# Grove_-_Multichannel_Gas_Sensor_v1_0.net
KiCad netlist of a schematic drawn in EAGLE
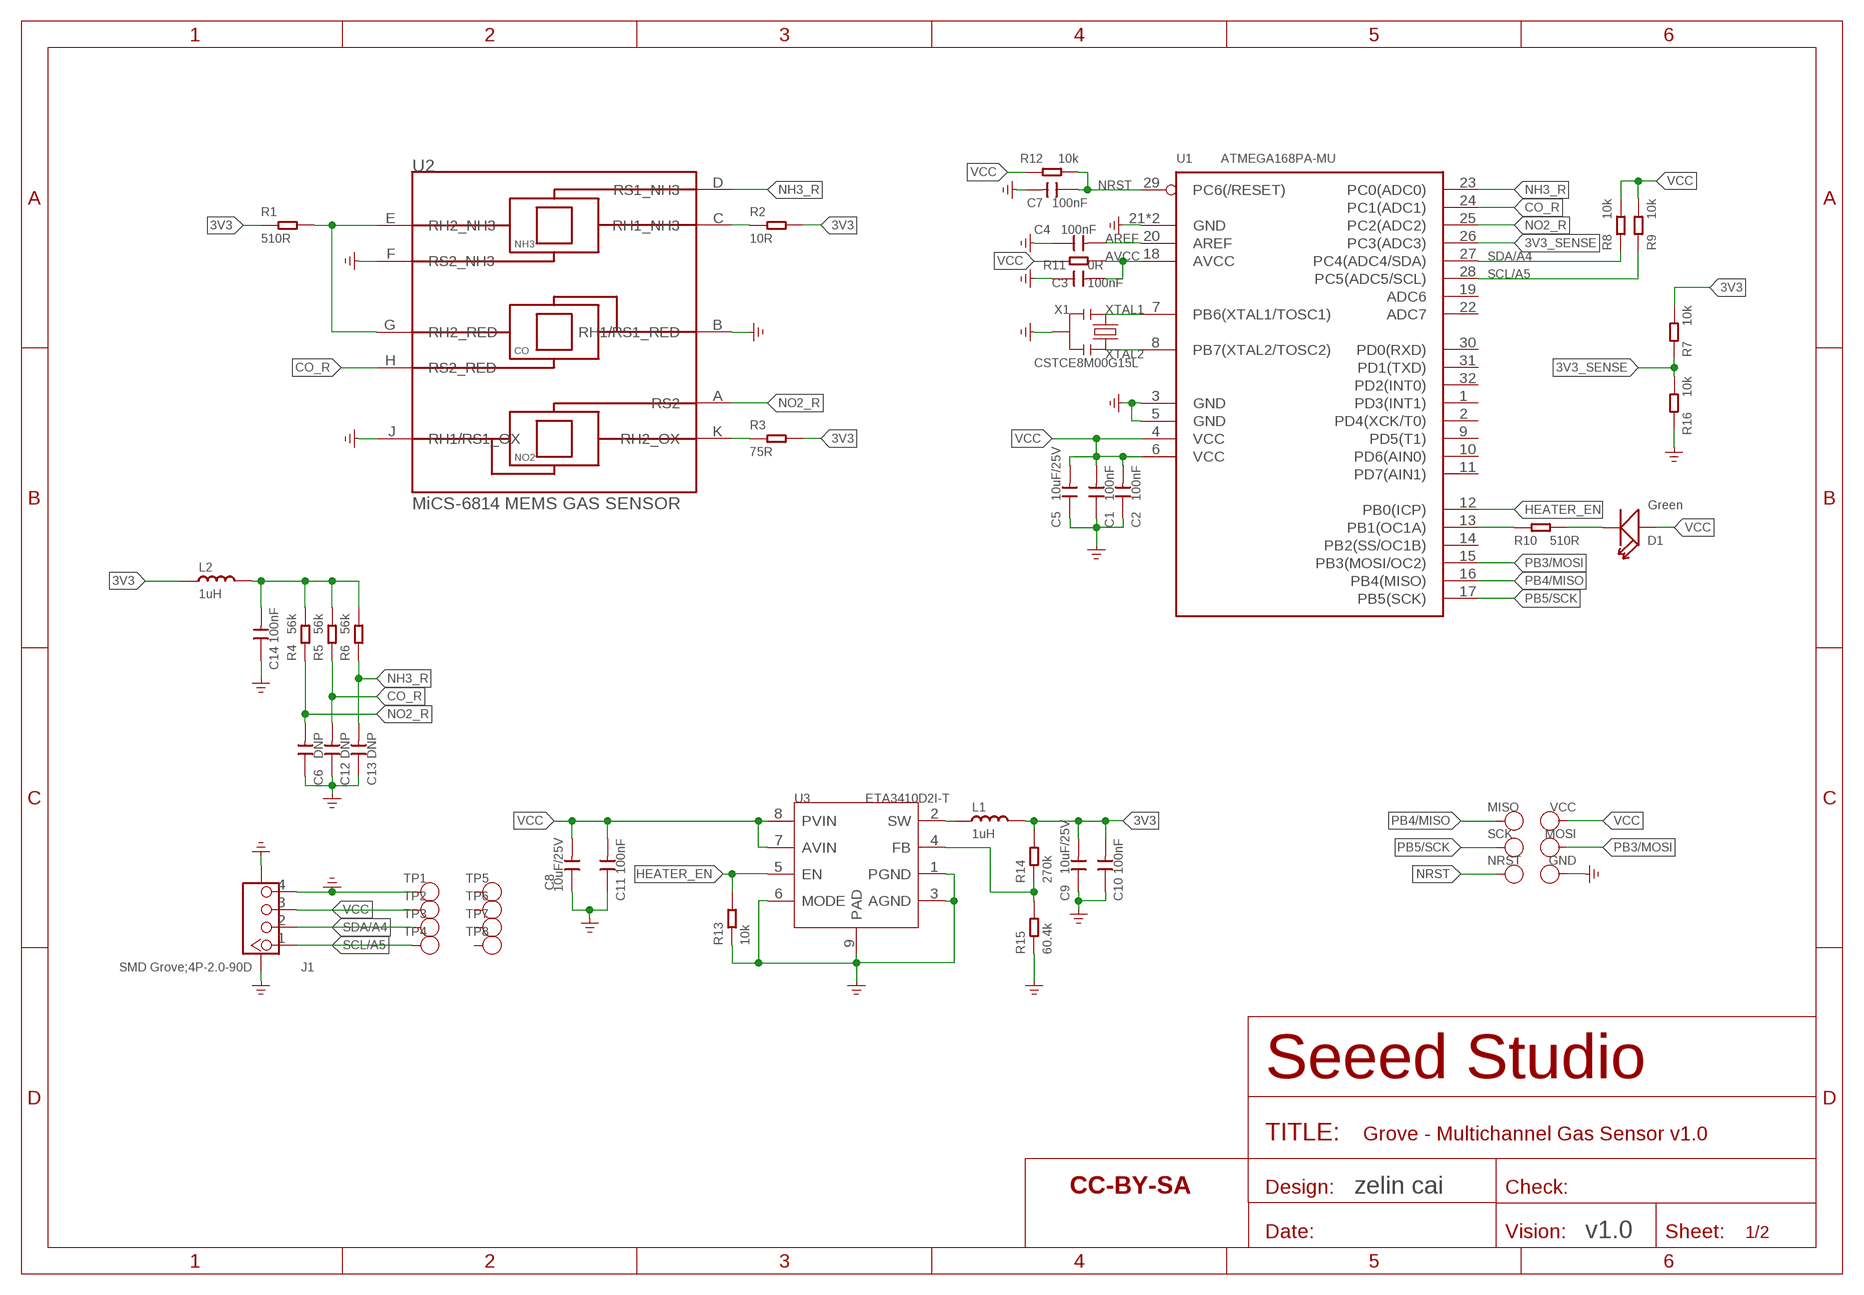
[diagram p0: schematic, sheet 1]

(export (version "E")
  (design (tool "Eeschema 10.0.6"))
  (components
    (comp (ref "C1")
      (value "100nF")
      (footprint "eagle-import:C0402")
      (libsource (lib "eagle-import") (part "CAP-0402"))
    )
    (comp (ref "C2")
      (value "100nF")
      (footprint "eagle-import:C0402")
      (libsource (lib "eagle-import") (part "CAP-0402"))
    )
    (comp (ref "C3")
      (value "100nF")
      (footprint "eagle-import:C0402")
      (libsource (lib "eagle-import") (part "CAP-0402"))
    )
    (comp (ref "C4")
      (value "100nF")
      (footprint "eagle-import:C0402")
      (libsource (lib "eagle-import") (part "CAP-0402"))
    )
    (comp (ref "C5")
      (value "10uF/25V")
      (footprint "eagle-import:C0805")
      (libsource (lib "eagle-import") (part "CAP-0805"))
    )
    (comp (ref "C6")
      (value "DNP")
      (footprint "eagle-import:C0402")
      (libsource (lib "eagle-import") (part "CAP-0402"))
    )
    (comp (ref "C7")
      (value "100nF")
      (footprint "eagle-import:C0402")
      (libsource (lib "eagle-import") (part "CAP-0402"))
    )
    (comp (ref "C8")
      (value "10uF/25V")
      (footprint "eagle-import:C0805")
      (libsource (lib "eagle-import") (part "CAP-0805"))
    )
    (comp (ref "C9")
      (value "10uF/25V")
      (footprint "eagle-import:C0805")
      (libsource (lib "eagle-import") (part "CAP-0805"))
    )
    (comp (ref "C10")
      (value "100nF")
      (footprint "eagle-import:C0402")
      (libsource (lib "eagle-import") (part "CAP-0402"))
    )
    (comp (ref "C11")
      (value "100nF")
      (footprint "eagle-import:C0402")
      (libsource (lib "eagle-import") (part "CAP-0402"))
    )
    (comp (ref "C12")
      (value "DNP")
      (footprint "eagle-import:C0402")
      (libsource (lib "eagle-import") (part "CAP-0402"))
    )
    (comp (ref "C13")
      (value "DNP")
      (footprint "eagle-import:C0402")
      (libsource (lib "eagle-import") (part "CAP-0402"))
    )
    (comp (ref "C14")
      (value "100nF")
      (footprint "eagle-import:C0402")
      (libsource (lib "eagle-import") (part "CAP-0402"))
    )
    (comp (ref "D1")
      (value "Green")
      (footprint "eagle-import:LED-0402")
      (libsource (lib "eagle-import") (part "LED'0402'"))
    )
    (comp (ref "GND")
      (value "GND")
      (footprint "eagle-import:TP-D45MIL")
      (fields (field (name "PARTNO") "DNP"))
      (libsource (lib "eagle-import") (part "TEST-POINT'4545'"))
    )
    (comp (ref "J1")
      (value "SMD Grove;4P-2.0-90D")
      (footprint "eagle-import:HW4-SMD-2.0-90D")
      (libsource (lib "eagle-import") (part "GROVE-CONNECTOR-SMD'90D'"))
    )
    (comp (ref "L1")
      (value "1uH")
      (footprint "eagle-import:L0603")
      (libsource (lib "eagle-import") (part "INDUCTOR/FERRITE-BEAD'0603'"))
    )
    (comp (ref "L2")
      (value "1uH")
      (footprint "eagle-import:L0603")
      (libsource (lib "eagle-import") (part "INDUCTOR/FERRITE-BEAD'0603'"))
    )
    (comp (ref "MISO")
      (value "MISO")
      (footprint "eagle-import:TP-D45MIL")
      (fields (field (name "PARTNO") "DNP"))
      (libsource (lib "eagle-import") (part "TEST-POINT'4545'"))
    )
    (comp (ref "MOSI")
      (value "MOSI")
      (footprint "eagle-import:TP-D45MIL")
      (fields (field (name "PARTNO") "DNP"))
      (libsource (lib "eagle-import") (part "TEST-POINT'4545'"))
    )
    (comp (ref "NRST")
      (value "NRST")
      (footprint "eagle-import:TP-D45MIL")
      (fields (field (name "PARTNO") "DNP"))
      (libsource (lib "eagle-import") (part "TEST-POINT'4545'"))
    )
    (comp (ref "R1")
      (value "510R")
      (footprint "eagle-import:R0402")
      (libsource (lib "eagle-import") (part "RES-0402"))
    )
    (comp (ref "R2")
      (value "10R")
      (footprint "eagle-import:R0402")
      (libsource (lib "eagle-import") (part "RES-0402"))
    )
    (comp (ref "R3")
      (value "75R")
      (footprint "eagle-import:R0402")
      (libsource (lib "eagle-import") (part "RES-0402"))
    )
    (comp (ref "R4")
      (value "56k")
      (footprint "eagle-import:R0402")
      (libsource (lib "eagle-import") (part "RES-0402"))
    )
    (comp (ref "R5")
      (value "56k")
      (footprint "eagle-import:R0402")
      (libsource (lib "eagle-import") (part "RES-0402"))
    )
    (comp (ref "R6")
      (value "56k")
      (footprint "eagle-import:R0402")
      (libsource (lib "eagle-import") (part "RES-0402"))
    )
    (comp (ref "R7")
      (value "10k")
      (footprint "eagle-import:R0402")
      (libsource (lib "eagle-import") (part "RES-0402"))
    )
    (comp (ref "R8")
      (value "10k")
      (footprint "eagle-import:R0402")
      (libsource (lib "eagle-import") (part "RES-0402"))
    )
    (comp (ref "R9")
      (value "10k")
      (footprint "eagle-import:R0402")
      (libsource (lib "eagle-import") (part "RES-0402"))
    )
    (comp (ref "R10")
      (value "510R")
      (footprint "eagle-import:R0402")
      (libsource (lib "eagle-import") (part "RES-0402"))
    )
    (comp (ref "R11")
      (value "0R")
      (footprint "eagle-import:R0402")
      (libsource (lib "eagle-import") (part "RES-0402"))
    )
    (comp (ref "R12")
      (value "10k")
      (footprint "eagle-import:R0402")
      (libsource (lib "eagle-import") (part "RES-0402"))
    )
    (comp (ref "R13")
      (value "10k")
      (footprint "eagle-import:R0402")
      (libsource (lib "eagle-import") (part "RES-0402"))
    )
    (comp (ref "R14")
      (value "270k")
      (footprint "eagle-import:R0402")
      (libsource (lib "eagle-import") (part "RES-0402"))
    )
    (comp (ref "R15")
      (value "60.4k")
      (footprint "eagle-import:R0402")
      (libsource (lib "eagle-import") (part "RES-0402"))
    )
    (comp (ref "R16")
      (value "10k")
      (footprint "eagle-import:R0402")
      (libsource (lib "eagle-import") (part "RES-0402"))
    )
    (comp (ref "SCK")
      (value "SCK")
      (footprint "eagle-import:TP-D45MIL")
      (fields (field (name "PARTNO") "DNP"))
      (libsource (lib "eagle-import") (part "TEST-POINT'4545'"))
    )
    (comp (ref "TP1")
      (value "GND")
      (footprint "eagle-import:TP-D45MIL")
      (fields (field (name "PARTNO") "DNP"))
      (libsource (lib "eagle-import") (part "TEST-POINT'4545'"))
    )
    (comp (ref "TP2")
      (value "VCC")
      (footprint "eagle-import:TP-D45MIL")
      (fields (field (name "PARTNO") "DNP"))
      (libsource (lib "eagle-import") (part "TEST-POINT'4545'"))
    )
    (comp (ref "TP3")
      (value "SDA")
      (footprint "eagle-import:TP-D45MIL")
      (fields (field (name "PARTNO") "DNP"))
      (libsource (lib "eagle-import") (part "TEST-POINT'4545'"))
    )
    (comp (ref "TP4")
      (value "SCL")
      (footprint "eagle-import:TP-D45MIL")
      (fields (field (name "PARTNO") "DNP"))
      (libsource (lib "eagle-import") (part "TEST-POINT'4545'"))
    )
    (comp (ref "TP5")
      (value "NC")
      (footprint "eagle-import:TP-D45MIL")
      (fields (field (name "PARTNO") "DNP"))
      (libsource (lib "eagle-import") (part "TEST-POINT'4545'"))
    )
    (comp (ref "TP6")
      (value "NC")
      (footprint "eagle-import:TP-D45MIL")
      (fields (field (name "PARTNO") "DNP"))
      (libsource (lib "eagle-import") (part "TEST-POINT'4545'"))
    )
    (comp (ref "TP7")
      (value "NC")
      (footprint "eagle-import:TP-D45MIL")
      (fields (field (name "PARTNO") "DNP"))
      (libsource (lib "eagle-import") (part "TEST-POINT'4545'"))
    )
    (comp (ref "TP8")
      (value "NC")
      (footprint "eagle-import:TP-D45MIL")
      (fields (field (name "PARTNO") "DNP"))
      (libsource (lib "eagle-import") (part "TEST-POINT'4545'"))
    )
    (comp (ref "U$1")
      (value "Xadow-Multichanel Gas Sensor")
      (footprint "eagle-import:SEEEDSTUDIO-PCB-FRAME")
      (libsource (lib "eagle-import") (part "SEEEDSTUDIO-OPEN-SCH-FRAME"))
    )
    (comp (ref "U1")
      (value "ATMEGA168PA-MU")
      (footprint "eagle-import:QFN32G-0.5-5X5MM")
      (libsource (lib "eagle-import") (part "MCU-ATMEGA8/168/328MU"))
    )
    (comp (ref "U2")
      (value "MiCS-6814")
      (footprint "eagle-import:MICS-6814")
      (libsource (lib "eagle-import") (part "MICS-6814"))
    )
    (comp (ref "U3")
      (value "ETA3410D2I-T")
      (footprint "eagle-import:DFN8G-0.5-2X2MM")
      (libsource (lib "eagle-import") (part "CONVERTER-ETA3410"))
    )
    (comp (ref "VCC")
      (value "VCC")
      (footprint "eagle-import:TP-D45MIL")
      (fields (field (name "PARTNO") "DNP"))
      (libsource (lib "eagle-import") (part "TEST-POINT'4545'"))
    )
    (comp (ref "X1")
      (value "CSTCE8M00G15L")
      (footprint "eagle-import:RESONATOR3-SMD-3.6X1.3X0.8MM")
      (libsource (lib "eagle-import") (part "CRYSTAL-RESONATOR'SMD'"))
    )
  )
  (nets
    (net (code "1") (name "3V3") (class "Default")
      (node (ref "C10") (pin "2") (pinfunction "2_2") (pintype "passive"))
      (node (ref "C9") (pin "2") (pinfunction "2_2") (pintype "passive"))
      (node (ref "L1") (pin "2") (pinfunction "2_2") (pintype "passive"))
      (node (ref "L2") (pin "1") (pinfunction "1_1") (pintype "passive"))
      (node (ref "R1") (pin "1") (pinfunction "1_1") (pintype "passive"))
      (node (ref "R14") (pin "2") (pinfunction "2_2") (pintype "passive"))
      (node (ref "R2") (pin "2") (pinfunction "2_2") (pintype "passive"))
      (node (ref "R3") (pin "2") (pinfunction "2_2") (pintype "passive"))
      (node (ref "R7") (pin "1") (pinfunction "1_1") (pintype "passive"))
    )
    (net (code "2") (name "3V3_SENSE") (class "Default")
      (node (ref "R16") (pin "1") (pinfunction "1_1") (pintype "passive"))
      (node (ref "R7") (pin "2") (pinfunction "2_2") (pintype "passive"))
      (node (ref "U1") (pin "26") (pinfunction "PC3(ADC3)_26") (pintype "bidirectional"))
    )
    (net (code "3") (name "AREF") (class "Default")
      (node (ref "C4") (pin "2") (pinfunction "2_2") (pintype "passive"))
      (node (ref "U1") (pin "20") (pinfunction "AREF_20") (pintype "bidirectional"))
    )
    (net (code "4") (name "AVCC") (class "Default")
      (node (ref "C3") (pin "2") (pinfunction "2_2") (pintype "passive"))
      (node (ref "R11") (pin "2") (pinfunction "2_2") (pintype "passive"))
      (node (ref "U1") (pin "18") (pinfunction "AVCC_18") (pintype "bidirectional"))
    )
    (net (code "5") (name "CO_R") (class "Default")
      (node (ref "C12") (pin "2") (pinfunction "2_2") (pintype "passive"))
      (node (ref "R5") (pin "1") (pinfunction "1_1") (pintype "passive"))
      (node (ref "U1") (pin "24") (pinfunction "PC1(ADC1)_24") (pintype "bidirectional"))
      (node (ref "U2") (pin "H") (pinfunction "RS2_RED_H") (pintype "bidirectional"))
    )
    (net (code "6") (name "GND") (class "Default")
      (node (ref "C1") (pin "1") (pinfunction "1_1") (pintype "passive"))
      (node (ref "C10") (pin "1") (pinfunction "1_1") (pintype "passive"))
      (node (ref "C11") (pin "1") (pinfunction "1_1") (pintype "passive"))
      (node (ref "C12") (pin "1") (pinfunction "1_1") (pintype "passive"))
      (node (ref "C13") (pin "1") (pinfunction "1_1") (pintype "passive"))
      (node (ref "C14") (pin "1") (pinfunction "1_1") (pintype "passive"))
      (node (ref "C2") (pin "1") (pinfunction "1_1") (pintype "passive"))
      (node (ref "C3") (pin "1") (pinfunction "1_1") (pintype "passive"))
      (node (ref "C4") (pin "1") (pinfunction "1_1") (pintype "passive"))
      (node (ref "C5") (pin "1") (pinfunction "1_1") (pintype "passive"))
      (node (ref "C6") (pin "1") (pinfunction "1_1") (pintype "passive"))
      (node (ref "C7") (pin "2") (pinfunction "2_2") (pintype "passive"))
      (node (ref "C8") (pin "1") (pinfunction "1_1") (pintype "passive"))
      (node (ref "C9") (pin "1") (pinfunction "1_1") (pintype "passive"))
      (node (ref "GND") (pin "T") (pinfunction "T_T") (pintype "bidirectional"))
      (node (ref "J1") (pin "4") (pinfunction "4_4") (pintype "bidirectional"))
      (node (ref "J1") (pin "SS1") (pinfunction "SS1_SS1") (pintype "bidirectional"))
      (node (ref "J1") (pin "SS2") (pinfunction "SS2_SS2") (pintype "bidirectional"))
      (node (ref "R13") (pin "1") (pinfunction "1_1") (pintype "passive"))
      (node (ref "R15") (pin "1") (pinfunction "1_1") (pintype "passive"))
      (node (ref "R16") (pin "2") (pinfunction "2_2") (pintype "passive"))
      (node (ref "TP1") (pin "T") (pinfunction "T_T") (pintype "bidirectional"))
      (node (ref "U1") (pin "21") (pinfunction "GND_21") (pintype "bidirectional"))
      (node (ref "U1") (pin "3") (pinfunction "GND_3") (pintype "bidirectional"))
      (node (ref "U1") (pin "33") (pinfunction "GND_33") (pintype "bidirectional"))
      (node (ref "U1") (pin "5") (pinfunction "GND_5") (pintype "bidirectional"))
      (node (ref "U2") (pin "B") (pinfunction "RH1/RS1_RED_B") (pintype "bidirectional"))
      (node (ref "U2") (pin "F") (pinfunction "RS2_NH3_F") (pintype "bidirectional"))
      (node (ref "U2") (pin "J") (pinfunction "RH1/RS1_OX_J") (pintype "bidirectional"))
      (node (ref "U3") (pin "1") (pinfunction "PGND_1") (pintype "bidirectional"))
      (node (ref "U3") (pin "3") (pinfunction "AGND_3") (pintype "bidirectional"))
      (node (ref "U3") (pin "6") (pinfunction "MODE_6") (pintype "bidirectional"))
      (node (ref "U3") (pin "9") (pinfunction "PAD_9") (pintype "bidirectional"))
      (node (ref "X1") (pin "2") (pinfunction "2_2") (pintype "passive"))
    )
    (net (code "7") (name "HEATER_EN") (class "Default")
      (node (ref "R13") (pin "2") (pinfunction "2_2") (pintype "passive"))
      (node (ref "U1") (pin "12") (pinfunction "PB0(ICP)_12") (pintype "bidirectional"))
      (node (ref "U3") (pin "5") (pinfunction "EN_5") (pintype "bidirectional"))
    )
    (net (code "8") (name "NH3_R") (class "Default")
      (node (ref "C13") (pin "2") (pinfunction "2_2") (pintype "passive"))
      (node (ref "R6") (pin "1") (pinfunction "1_1") (pintype "passive"))
      (node (ref "U1") (pin "23") (pinfunction "PC0(ADC0)_23") (pintype "bidirectional"))
      (node (ref "U2") (pin "D") (pinfunction "RS1_NH3_D") (pintype "bidirectional"))
    )
    (net (code "9") (name "NO2_R") (class "Default")
      (node (ref "C6") (pin "2") (pinfunction "2_2") (pintype "passive"))
      (node (ref "R4") (pin "1") (pinfunction "1_1") (pintype "passive"))
      (node (ref "U1") (pin "25") (pinfunction "PC2(ADC2)_25") (pintype "bidirectional"))
      (node (ref "U2") (pin "A") (pinfunction "RS2_A") (pintype "bidirectional"))
    )
    (net (code "10") (name "NRST") (class "Default")
      (node (ref "C7") (pin "1") (pinfunction "1_1") (pintype "passive"))
      (node (ref "NRST") (pin "T") (pinfunction "T_T") (pintype "bidirectional"))
      (node (ref "R12") (pin "1") (pinfunction "1_1") (pintype "passive"))
      (node (ref "U1") (pin "29") (pinfunction "PC6(/RESET)_29") (pintype "bidirectional"))
    )
    (net (code "11") (name "Net-(C14-Pad2)") (class "Default")
      (node (ref "C14") (pin "2") (pinfunction "2_2") (pintype "passive"))
      (node (ref "L2") (pin "2") (pinfunction "2_2") (pintype "passive"))
      (node (ref "R4") (pin "2") (pinfunction "2_2") (pintype "passive"))
      (node (ref "R5") (pin "2") (pinfunction "2_2") (pintype "passive"))
      (node (ref "R6") (pin "2") (pinfunction "2_2") (pintype "passive"))
    )
    (net (code "12") (name "Net-(D1-Pad-)") (class "Default")
      (node (ref "D1") (pin "-") (pinfunction "-_-") (pintype "passive"))
      (node (ref "R10") (pin "2") (pinfunction "2_2") (pintype "passive"))
    )
    (net (code "13") (name "Net-(U1-PB1(OC1A))") (class "Default")
      (node (ref "R10") (pin "1") (pinfunction "1_1") (pintype "passive"))
      (node (ref "U1") (pin "13") (pinfunction "PB1(OC1A)_13") (pintype "bidirectional"))
    )
    (net (code "14") (name "Net-(U2-RH1_NH3)") (class "Default")
      (node (ref "R2") (pin "1") (pinfunction "1_1") (pintype "passive"))
      (node (ref "U2") (pin "C") (pinfunction "RH1_NH3_C") (pintype "bidirectional"))
    )
    (net (code "15") (name "Net-(U2-RH2_NH3)") (class "Default")
      (node (ref "R1") (pin "2") (pinfunction "2_2") (pintype "passive"))
      (node (ref "U2") (pin "E") (pinfunction "RH2_NH3_E") (pintype "bidirectional"))
      (node (ref "U2") (pin "G") (pinfunction "RH2_RED_G") (pintype "bidirectional"))
    )
    (net (code "16") (name "Net-(U2-RH2_OX)") (class "Default")
      (node (ref "R3") (pin "1") (pinfunction "1_1") (pintype "passive"))
      (node (ref "U2") (pin "K") (pinfunction "RH2_OX_K") (pintype "bidirectional"))
    )
    (net (code "17") (name "Net-(U3-FB)") (class "Default")
      (node (ref "R14") (pin "1") (pinfunction "1_1") (pintype "passive"))
      (node (ref "R15") (pin "2") (pinfunction "2_2") (pintype "passive"))
      (node (ref "U3") (pin "4") (pinfunction "FB_4") (pintype "bidirectional"))
    )
    (net (code "18") (name "Net-(U3-SW)") (class "Default")
      (node (ref "L1") (pin "1") (pinfunction "1_1") (pintype "passive"))
      (node (ref "U3") (pin "2") (pinfunction "SW_2") (pintype "bidirectional"))
    )
    (net (code "19") (name "PB3{slash}MOSI") (class "Default")
      (node (ref "MOSI") (pin "T") (pinfunction "T_T") (pintype "bidirectional"))
      (node (ref "U1") (pin "15") (pinfunction "PB3(MOSI/OC2)_15") (pintype "bidirectional"))
    )
    (net (code "20") (name "PB4{slash}MISO") (class "Default")
      (node (ref "MISO") (pin "T") (pinfunction "T_T") (pintype "bidirectional"))
      (node (ref "U1") (pin "16") (pinfunction "PB4(MISO)_16") (pintype "bidirectional"))
    )
    (net (code "21") (name "PB5{slash}SCK") (class "Default")
      (node (ref "SCK") (pin "T") (pinfunction "T_T") (pintype "bidirectional"))
      (node (ref "U1") (pin "17") (pinfunction "PB5(SCK)_17") (pintype "bidirectional"))
    )
    (net (code "22") (name "SCL{slash}A5") (class "Default")
      (node (ref "J1") (pin "1") (pinfunction "1_1") (pintype "bidirectional"))
      (node (ref "R9") (pin "2") (pinfunction "2_2") (pintype "passive"))
      (node (ref "TP4") (pin "T") (pinfunction "T_T") (pintype "bidirectional"))
      (node (ref "U1") (pin "28") (pinfunction "PC5(ADC5/SCL)_28") (pintype "bidirectional"))
    )
    (net (code "23") (name "SDA{slash}A4") (class "Default")
      (node (ref "J1") (pin "2") (pinfunction "2_2") (pintype "bidirectional"))
      (node (ref "R8") (pin "2") (pinfunction "2_2") (pintype "passive"))
      (node (ref "TP3") (pin "T") (pinfunction "T_T") (pintype "bidirectional"))
      (node (ref "U1") (pin "27") (pinfunction "PC4(ADC4/SDA)_27") (pintype "bidirectional"))
    )
    (net (code "24") (name "VCC") (class "Default")
      (node (ref "C1") (pin "2") (pinfunction "2_2") (pintype "passive"))
      (node (ref "C11") (pin "2") (pinfunction "2_2") (pintype "passive"))
      (node (ref "C2") (pin "2") (pinfunction "2_2") (pintype "passive"))
      (node (ref "C5") (pin "2") (pinfunction "2_2") (pintype "passive"))
      (node (ref "C8") (pin "2") (pinfunction "2_2") (pintype "passive"))
      (node (ref "D1") (pin "+") (pinfunction "+_+") (pintype "passive"))
      (node (ref "J1") (pin "3") (pinfunction "3_3") (pintype "bidirectional"))
      (node (ref "R11") (pin "1") (pinfunction "1_1") (pintype "passive"))
      (node (ref "R12") (pin "2") (pinfunction "2_2") (pintype "passive"))
      (node (ref "R8") (pin "1") (pinfunction "1_1") (pintype "passive"))
      (node (ref "R9") (pin "1") (pinfunction "1_1") (pintype "passive"))
      (node (ref "TP2") (pin "T") (pinfunction "T_T") (pintype "bidirectional"))
      (node (ref "U1") (pin "4") (pinfunction "VCC_4") (pintype "bidirectional"))
      (node (ref "U1") (pin "6") (pinfunction "VCC_6") (pintype "bidirectional"))
      (node (ref "U3") (pin "7") (pinfunction "AVIN_7") (pintype "bidirectional"))
      (node (ref "U3") (pin "8") (pinfunction "PVIN_8") (pintype "bidirectional"))
      (node (ref "VCC") (pin "T") (pinfunction "T_T") (pintype "bidirectional"))
    )
    (net (code "25") (name "XTAL1") (class "Default")
      (node (ref "U1") (pin "7") (pinfunction "PB6(XTAL1/TOSC1)_7") (pintype "bidirectional"))
      (node (ref "X1") (pin "1") (pinfunction "1_1") (pintype "passive"))
    )
    (net (code "26") (name "XTAL2") (class "Default")
      (node (ref "U1") (pin "8") (pinfunction "PB7(XTAL2/TOSC2)_8") (pintype "bidirectional"))
      (node (ref "X1") (pin "3") (pinfunction "3_3") (pintype "passive"))
    )
    (net (code "27") (name "unconnected-(TP5-PadT)") (class "Default")
      (node (ref "TP5") (pin "T") (pinfunction "T_T") (pintype "bidirectional"))
    )
    (net (code "28") (name "unconnected-(TP6-PadT)") (class "Default")
      (node (ref "TP6") (pin "T") (pinfunction "T_T") (pintype "bidirectional"))
    )
    (net (code "29") (name "unconnected-(TP7-PadT)") (class "Default")
      (node (ref "TP7") (pin "T") (pinfunction "T_T") (pintype "bidirectional"))
    )
    (net (code "30") (name "unconnected-(TP8-PadT)") (class "Default")
      (node (ref "TP8") (pin "T") (pinfunction "T_T") (pintype "bidirectional"))
    )
    (net (code "31") (name "unconnected-(U1-ADC6-Pad19)") (class "Default")
      (node (ref "U1") (pin "19") (pinfunction "ADC6_19") (pintype "bidirectional"))
    )
    (net (code "32") (name "unconnected-(U1-ADC7-Pad22)") (class "Default")
      (node (ref "U1") (pin "22") (pinfunction "ADC7_22") (pintype "bidirectional"))
    )
    (net (code "33") (name "unconnected-(U1-PB2(SS{slash}OC1B)-Pad14)") (class "Default")
      (node (ref "U1") (pin "14") (pinfunction "PB2(SS/OC1B)_14") (pintype "bidirectional"))
    )
    (net (code "34") (name "unconnected-(U1-PD0(RXD)-Pad30)") (class "Default")
      (node (ref "U1") (pin "30") (pinfunction "PD0(RXD)_30") (pintype "bidirectional"))
    )
    (net (code "35") (name "unconnected-(U1-PD1(TXD)-Pad31)") (class "Default")
      (node (ref "U1") (pin "31") (pinfunction "PD1(TXD)_31") (pintype "bidirectional"))
    )
    (net (code "36") (name "unconnected-(U1-PD2(INT0)-Pad32)") (class "Default")
      (node (ref "U1") (pin "32") (pinfunction "PD2(INT0)_32") (pintype "bidirectional"))
    )
    (net (code "37") (name "unconnected-(U1-PD3(INT1)-Pad1)") (class "Default")
      (node (ref "U1") (pin "1") (pinfunction "PD3(INT1)_1") (pintype "bidirectional"))
    )
    (net (code "38") (name "unconnected-(U1-PD4(XCK{slash}T0)-Pad2)") (class "Default")
      (node (ref "U1") (pin "2") (pinfunction "PD4(XCK/T0)_2") (pintype "bidirectional"))
    )
    (net (code "39") (name "unconnected-(U1-PD5(T1)-Pad9)") (class "Default")
      (node (ref "U1") (pin "9") (pinfunction "PD5(T1)_9") (pintype "bidirectional"))
    )
    (net (code "40") (name "unconnected-(U1-PD6(AIN0)-Pad10)") (class "Default")
      (node (ref "U1") (pin "10") (pinfunction "PD6(AIN0)_10") (pintype "bidirectional"))
    )
    (net (code "41") (name "unconnected-(U1-PD7(AIN1)-Pad11)") (class "Default")
      (node (ref "U1") (pin "11") (pinfunction "PD7(AIN1)_11") (pintype "bidirectional"))
    )
  )
)
